# Zio_Qwiic_Power_adapter.net
KiCad netlist of a schematic drawn in EAGLE
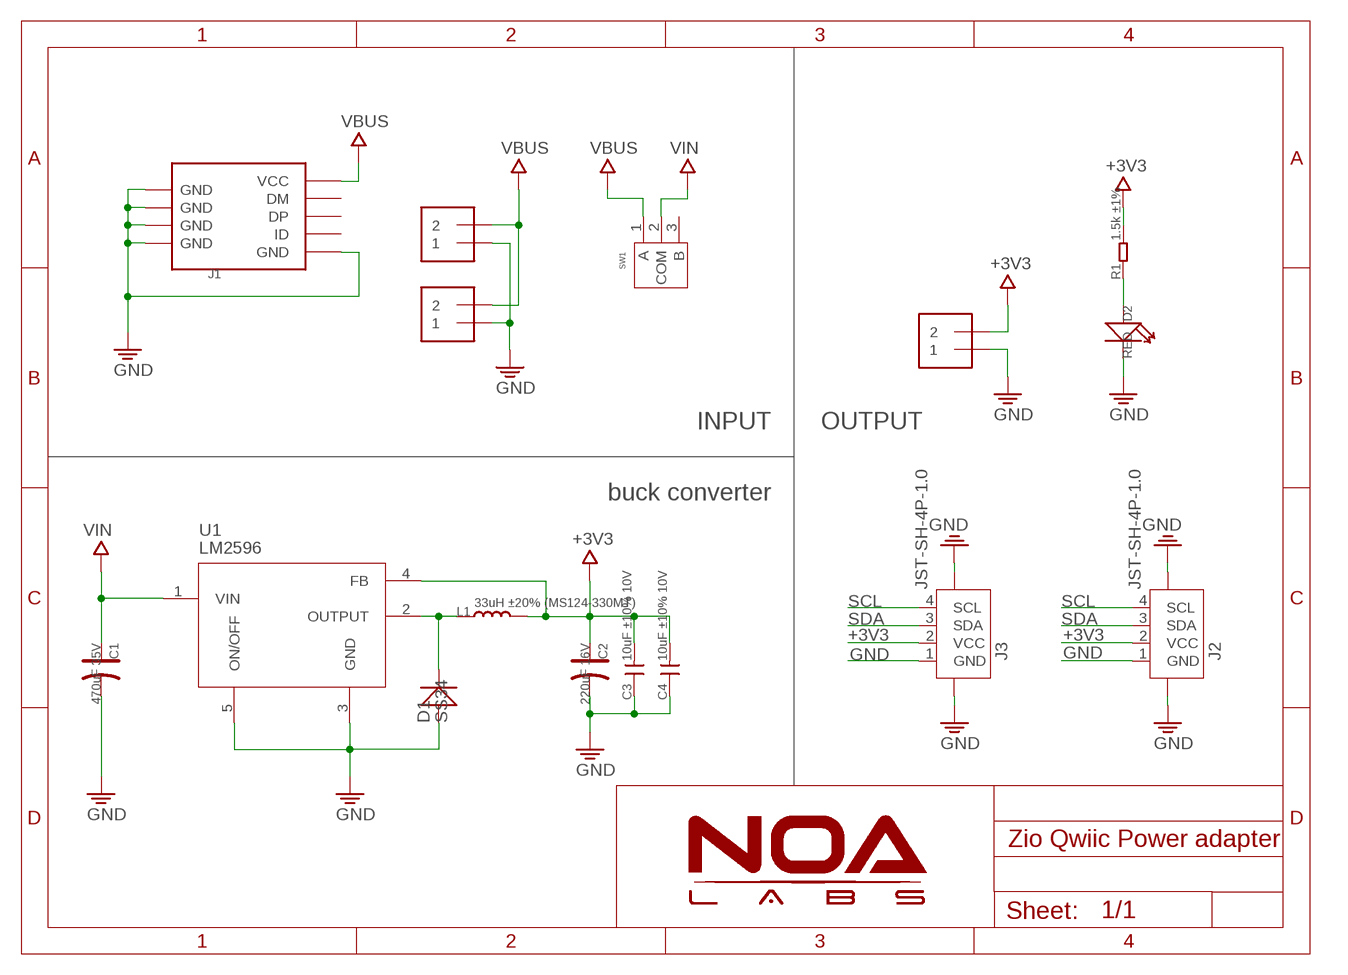
[diagram p0: schematic, sheet 1]

(export (version "E")
  (design (tool "Eeschema 10.0.6"))
  (components
    (comp (ref "C1")
      (value "470uF 35V")
      (footprint "eagle-import:ELECTRO-SMD-G-10MM")
      (libsource (lib "eagle-import") (part "Discretex_CAP-ELECTRO-G"))
    )
    (comp (ref "C2")
      (value "220uF 16V")
      (footprint "eagle-import:ELECTRO-SMD-C-6MM")
      (libsource (lib "eagle-import") (part "CAP-ELECTRO-C"))
    )
    (comp (ref "C3")
      (value "10uF ±10% 10V")
      (footprint "eagle-import:C1206")
      (libsource (lib "eagle-import") (part "C-1206"))
    )
    (comp (ref "C4")
      (value "10uF ±10% 10V")
      (footprint "eagle-import:C1206")
      (libsource (lib "eagle-import") (part "C-1206"))
    )
    (comp (ref "D1")
      (value "SS34")
      (footprint "eagle-import:SMA")
      (libsource (lib "eagle-import") (part "D-B130L-13-F"))
    )
    (comp (ref "D2")
      (value "RED")
      (footprint "eagle-import:LED-0603")
      (libsource (lib "eagle-import") (part "LED'0603'"))
    )
    (comp (ref "J1")
      (value "USB-MICROE")
      (footprint "eagle-import:MICRO-SMD")
      (libsource (lib "eagle-import") (part "USB-MICROE"))
    )
    (comp (ref "J2")
      (value "JST-SH-4P-1.0")
      (footprint "eagle-import:JST-SH-4P")
      (libsource (lib "eagle-import") (part "JST-SH-4P-1.0"))
    )
    (comp (ref "J3")
      (value "JST-SH-4P-1.0")
      (footprint "eagle-import:JST-SH-4P")
      (libsource (lib "eagle-import") (part "JST-SH-4P-1.0"))
    )
    (comp (ref "J4")
      (value "TERMBLOCK_1X2-3.5MM")
      (footprint "eagle-import:1X2-3.5MM")
      (libsource (lib "eagle-import") (part "TERMBLOCK_1X2-3.5MM"))
    )
    (comp (ref "J5")
      (value "TERMBLOCK_1X2-3.5MM")
      (footprint "eagle-import:1X2-3.5MM")
      (libsource (lib "eagle-import") (part "TERMBLOCK_1X2-3.5MM"))
    )
    (comp (ref "J6")
      (value "TERMBLOCK_1X2-3.5MM")
      (footprint "eagle-import:1X2-3.5MM")
      (libsource (lib "eagle-import") (part "TERMBLOCK_1X2-3.5MM"))
    )
    (comp (ref "L1")
      (value "33uH ±20% (MS124-330MT)")
      (footprint "eagle-import:L-12.2_12.2")
      (libsource (lib "eagle-import") (part "L12.212.2"))
    )
    (comp (ref "R1")
      (value "1.5k ±1%")
      (footprint "eagle-import:R0603")
      (libsource (lib "eagle-import") (part "R-0603"))
    )
    (comp (ref "SW1")
      (value "SWITCH-2H-3P2A/3A")
      (footprint "eagle-import:3P-2CH-12.7X6.6X6.35H")
      (libsource (lib "eagle-import") (part "SWITCH-2H-3P2A/3A"))
    )
    (comp (ref "U1")
      (value "LM2596")
      (footprint "eagle-import:TO-263")
      (libsource (lib "eagle-import") (part "LM2596"))
    )
  )
  (nets
    (net (code "1") (name "+3V3") (class "Default")
      (node (ref "C2") (pin "+") (pinfunction "+_+") (pintype "passive"))
      (node (ref "C3") (pin "2") (pinfunction "2_2") (pintype "passive"))
      (node (ref "C4") (pin "2") (pinfunction "2_2") (pintype "passive"))
      (node (ref "J2") (pin "2") (pinfunction "VCC_2") (pintype "bidirectional"))
      (node (ref "J3") (pin "2") (pinfunction "VCC_2") (pintype "bidirectional"))
      (node (ref "J5") (pin "2") (pinfunction "2_2") (pintype "passive"))
      (node (ref "L1") (pin "2") (pinfunction "2_2") (pintype "passive"))
      (node (ref "R1") (pin "2") (pinfunction "2_2") (pintype "passive"))
      (node (ref "U1") (pin "4") (pinfunction "FB_4") (pintype "bidirectional"))
    )
    (net (code "2") (name "/SCL") (class "Default")
      (node (ref "J2") (pin "4") (pinfunction "SCL_4") (pintype "bidirectional"))
      (node (ref "J3") (pin "4") (pinfunction "SCL_4") (pintype "bidirectional"))
    )
    (net (code "3") (name "/SDA") (class "Default")
      (node (ref "J2") (pin "3") (pinfunction "SDA_3") (pintype "bidirectional"))
      (node (ref "J3") (pin "3") (pinfunction "SDA_3") (pintype "bidirectional"))
    )
    (net (code "4") (name "GND") (class "Default")
      (node (ref "C1") (pin "-") (pinfunction "-_-") (pintype "passive"))
      (node (ref "C2") (pin "-") (pinfunction "-_-") (pintype "passive"))
      (node (ref "C3") (pin "1") (pinfunction "1_1") (pintype "passive"))
      (node (ref "C4") (pin "1") (pinfunction "1_1") (pintype "passive"))
      (node (ref "D1") (pin "P$2") (pinfunction "+_P$2") (pintype "passive"))
      (node (ref "D2") (pin "-") (pinfunction "-_-") (pintype "passive"))
      (node (ref "J1") (pin "GND") (pinfunction "GND_GND") (pintype "bidirectional"))
      (node (ref "J1") (pin "S1") (pinfunction "GND_S1") (pintype "bidirectional"))
      (node (ref "J1") (pin "S1@1") (pinfunction "GND_S1@1") (pintype "bidirectional"))
      (node (ref "J1") (pin "S1@2") (pinfunction "GND_S1@2") (pintype "bidirectional"))
      (node (ref "J1") (pin "S2") (pinfunction "GND_S2") (pintype "bidirectional"))
      (node (ref "J1") (pin "S2@1") (pinfunction "GND_S2@1") (pintype "bidirectional"))
      (node (ref "J1") (pin "S2@2") (pinfunction "GND_S2@2") (pintype "bidirectional"))
      (node (ref "J1") (pin "S3") (pinfunction "GND_S3") (pintype "bidirectional"))
      (node (ref "J1") (pin "S3@1") (pinfunction "GND_S3@1") (pintype "bidirectional"))
      (node (ref "J1") (pin "S3@2") (pinfunction "GND_S3@2") (pintype "bidirectional"))
      (node (ref "J1") (pin "S4") (pinfunction "GND_S4") (pintype "bidirectional"))
      (node (ref "J1") (pin "S4@1") (pinfunction "GND_S4@1") (pintype "bidirectional"))
      (node (ref "J1") (pin "S4@2") (pinfunction "GND_S4@2") (pintype "bidirectional"))
      (node (ref "J1") (pin "S5") (pinfunction "GND_S5") (pintype "bidirectional"))
      (node (ref "J1") (pin "S6") (pinfunction "GND_S6") (pintype "bidirectional"))
      (node (ref "J2") (pin "1") (pinfunction "GND_1") (pintype "bidirectional"))
      (node (ref "J2") (pin "NC1") (pinfunction "5_NC1") (pintype "bidirectional"))
      (node (ref "J2") (pin "NC2") (pinfunction "6_NC2") (pintype "bidirectional"))
      (node (ref "J3") (pin "1") (pinfunction "GND_1") (pintype "bidirectional"))
      (node (ref "J3") (pin "NC1") (pinfunction "5_NC1") (pintype "bidirectional"))
      (node (ref "J3") (pin "NC2") (pinfunction "6_NC2") (pintype "bidirectional"))
      (node (ref "J4") (pin "1") (pinfunction "1_1") (pintype "passive"))
      (node (ref "J5") (pin "1") (pinfunction "1_1") (pintype "passive"))
      (node (ref "J6") (pin "1") (pinfunction "1_1") (pintype "passive"))
      (node (ref "U1") (pin "3") (pinfunction "GND_3") (pintype "bidirectional"))
      (node (ref "U1") (pin "5") (pinfunction "ON/OFF_5") (pintype "bidirectional"))
    )
    (net (code "5") (name "Net-(D1--)") (class "Default")
      (node (ref "D1") (pin "P$1") (pinfunction "-_P$1") (pintype "passive"))
      (node (ref "L1") (pin "1") (pinfunction "1_1") (pintype "passive"))
      (node (ref "U1") (pin "2") (pinfunction "OUTPUT_2") (pintype "bidirectional"))
    )
    (net (code "6") (name "Net-(D2-Pad+)") (class "Default")
      (node (ref "D2") (pin "+") (pinfunction "+_+") (pintype "passive"))
      (node (ref "R1") (pin "1") (pinfunction "1_1") (pintype "passive"))
    )
    (net (code "7") (name "VBUS") (class "Default")
      (node (ref "J1") (pin "VBUS") (pinfunction "VCC_VBUS") (pintype "bidirectional"))
      (node (ref "J4") (pin "2") (pinfunction "2_2") (pintype "passive"))
      (node (ref "J6") (pin "2") (pinfunction "2_2") (pintype "passive"))
      (node (ref "SW1") (pin "1") (pinfunction "A_1") (pintype "bidirectional"))
    )
    (net (code "8") (name "VIN") (class "Default")
      (node (ref "C1") (pin "+") (pinfunction "+_+") (pintype "passive"))
      (node (ref "SW1") (pin "2") (pinfunction "COM_2") (pintype "bidirectional"))
      (node (ref "U1") (pin "1") (pinfunction "VIN_1") (pintype "bidirectional"))
    )
    (net (code "9") (name "unconnected-(J1-DM-PadD-)") (class "Default")
      (node (ref "J1") (pin "D-") (pinfunction "DM_D-") (pintype "bidirectional"))
    )
    (net (code "10") (name "unconnected-(J1-DP-PadD+)") (class "Default")
      (node (ref "J1") (pin "D+") (pinfunction "DP_D+") (pintype "bidirectional"))
    )
    (net (code "11") (name "unconnected-(J1-PadID)") (class "Default")
      (node (ref "J1") (pin "ID") (pinfunction "ID_ID") (pintype "bidirectional"))
    )
    (net (code "12") (name "unconnected-(SW1-B-Pad3)") (class "Default")
      (node (ref "SW1") (pin "3") (pinfunction "B_3") (pintype "bidirectional"))
    )
  )
)
